# PWR-Buck-Boost_2V_to_5V.net
KiCad netlist of a schematic drawn in Altium Designer
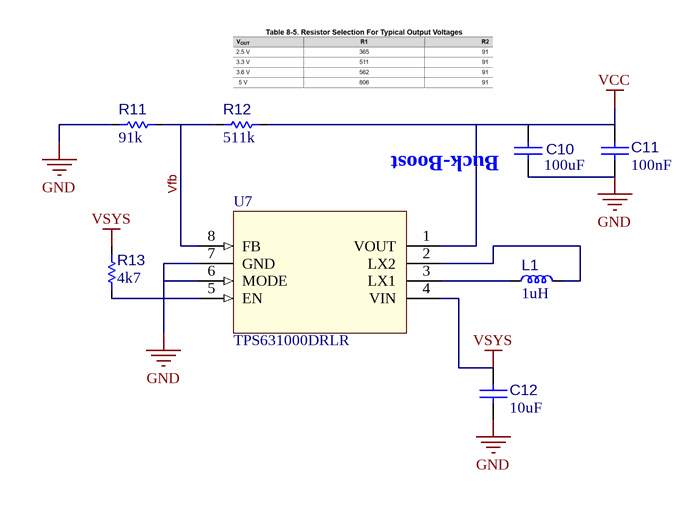
[diagram p0: PWR-Buck-Boost 2V to 5V.SchDoc]

(export (version "E")
  (design (tool "Eeschema 10.0.6"))
  (components
    (comp (ref "C10")
      (value "100uF")
      (footprint "C_3216[1206]")
      (description "Capacitor type 1")
      (fields (field (name "TOLERANCE") "20%") (field (name "Comment") "Cap 100uF 1206"))
      (libsource (lib "TEP_243-Altium_DBLib") (part "capacitor"))
    )
    (comp (ref "C11")
      (value "100nF")
      (footprint "C_1005[0402]")
      (description "Capacitor type 1")
      (fields (field (name "TOLERANCE") "10%") (field (name "Comment") "Cap 100nF 0402"))
      (libsource (lib "TEP_243-Altium_DBLib") (part "capacitor"))
    )
    (comp (ref "C12")
      (value "10uF")
      (footprint "C_2012[0805]")
      (description "Capacitor type 1")
      (fields (field (name "TOLERANCE") "10%") (field (name "Comment") "Cap 10uF 0805"))
      (libsource (lib "TEP_243-Altium_DBLib") (part "capacitor"))
    )
    (comp (ref "L1")
      (value "1uH")
      (footprint "L_3030[1212]")
      (description "Inductor type 1")
      (fields (field (name "TOLERANCE") "0,2") (field (name "Comment") "Ind 1UH 2.75A 51mOHM SMD"))
      (libsource (lib "TEP_243-Altium_DBLib") (part "inductor"))
    )
    (comp (ref "R11")
      (value "91k")
      (footprint "R_1005[0402]")
      (description "Resistor type 1")
      (fields (field (name "TOLERANCE") "1%") (field (name "Comment") "Res 91k 1% 0402"))
      (libsource (lib "TEP_243-Altium_DBLib") (part "resistor"))
    )
    (comp (ref "R12")
      (value "511k")
      (footprint "R_1005[0402]")
      (description "Resistor type 1")
      (fields (field (name "TOLERANCE") "1%") (field (name "Comment") "Res 511k 1% 0402"))
      (libsource (lib "TEP-AltiumLib-Passives-RLC") (part "resistor"))
    )
    (comp (ref "R13")
      (value "4k7")
      (footprint "R_1005[0402]")
      (description "Resistor type 1")
      (fields (field (name "TOLERANCE") "1%") (field (name "Comment") "Res 4k7 1% 0402"))
      (libsource (lib "TEP_243-Altium_DBLib") (part "resistor"))
    )
    (comp (ref "U7")
      (value "TPS631000DRLR")
      (footprint "U_SOT583_50P210X120X60-8")
      (description "buck-boost converter 1.5-A output current,")
      (libsource (lib "243-336_MP_Manette") (part "U_TPS631000DRLR"))
    )
  )
  (nets
    (net (code "1") (name "/Vfb") (class "Default")
      (node (ref "R11") (pin "1") (pinfunction "1_1") (pintype "passive"))
      (node (ref "R12") (pin "1") (pinfunction "1_1") (pintype "passive"))
      (node (ref "U7") (pin "8") (pinfunction "FB_8") (pintype "input"))
    )
    (net (code "2") (name "GND") (class "Default")
      (node (ref "C10") (pin "1") (pinfunction "1_1") (pintype "passive"))
      (node (ref "C11") (pin "1") (pinfunction "1_1") (pintype "passive"))
      (node (ref "C12") (pin "1") (pinfunction "1_1") (pintype "passive"))
      (node (ref "R11") (pin "2") (pinfunction "2_2") (pintype "passive"))
      (node (ref "U7") (pin "6") (pinfunction "MODE_6") (pintype "input"))
      (node (ref "U7") (pin "7") (pinfunction "GND_7") (pintype "power_in"))
    )
    (net (code "3") (name "Net-(U7-EN)") (class "Default")
      (node (ref "R13") (pin "1") (pinfunction "1_1") (pintype "passive"))
      (node (ref "U7") (pin "5") (pinfunction "EN_5") (pintype "input"))
    )
    (net (code "4") (name "Net-(U7-LX1)") (class "Default")
      (node (ref "L1") (pin "1") (pinfunction "1_1") (pintype "passive"))
      (node (ref "U7") (pin "3") (pinfunction "LX1_3") (pintype "power_in"))
    )
    (net (code "5") (name "Net-(U7-LX2)") (class "Default")
      (node (ref "L1") (pin "2") (pinfunction "2_2") (pintype "passive"))
      (node (ref "U7") (pin "2") (pinfunction "LX2_2") (pintype "power_in"))
    )
    (net (code "6") (name "VCC") (class "Default")
      (node (ref "C10") (pin "2") (pinfunction "2_2") (pintype "passive"))
      (node (ref "C11") (pin "2") (pinfunction "2_2") (pintype "passive"))
      (node (ref "R12") (pin "2") (pinfunction "2_2") (pintype "passive"))
      (node (ref "U7") (pin "1") (pinfunction "VOUT_1") (pintype "power_in"))
    )
    (net (code "7") (name "VSYS") (class "Default")
      (node (ref "C12") (pin "2") (pinfunction "2_2") (pintype "passive"))
      (node (ref "R13") (pin "2") (pinfunction "2_2") (pintype "passive"))
      (node (ref "U7") (pin "4") (pinfunction "VIN_4") (pintype "power_in"))
    )
  )
)
